# PMIC_Block.net
KiCad netlist of a schematic drawn in Altium Designer
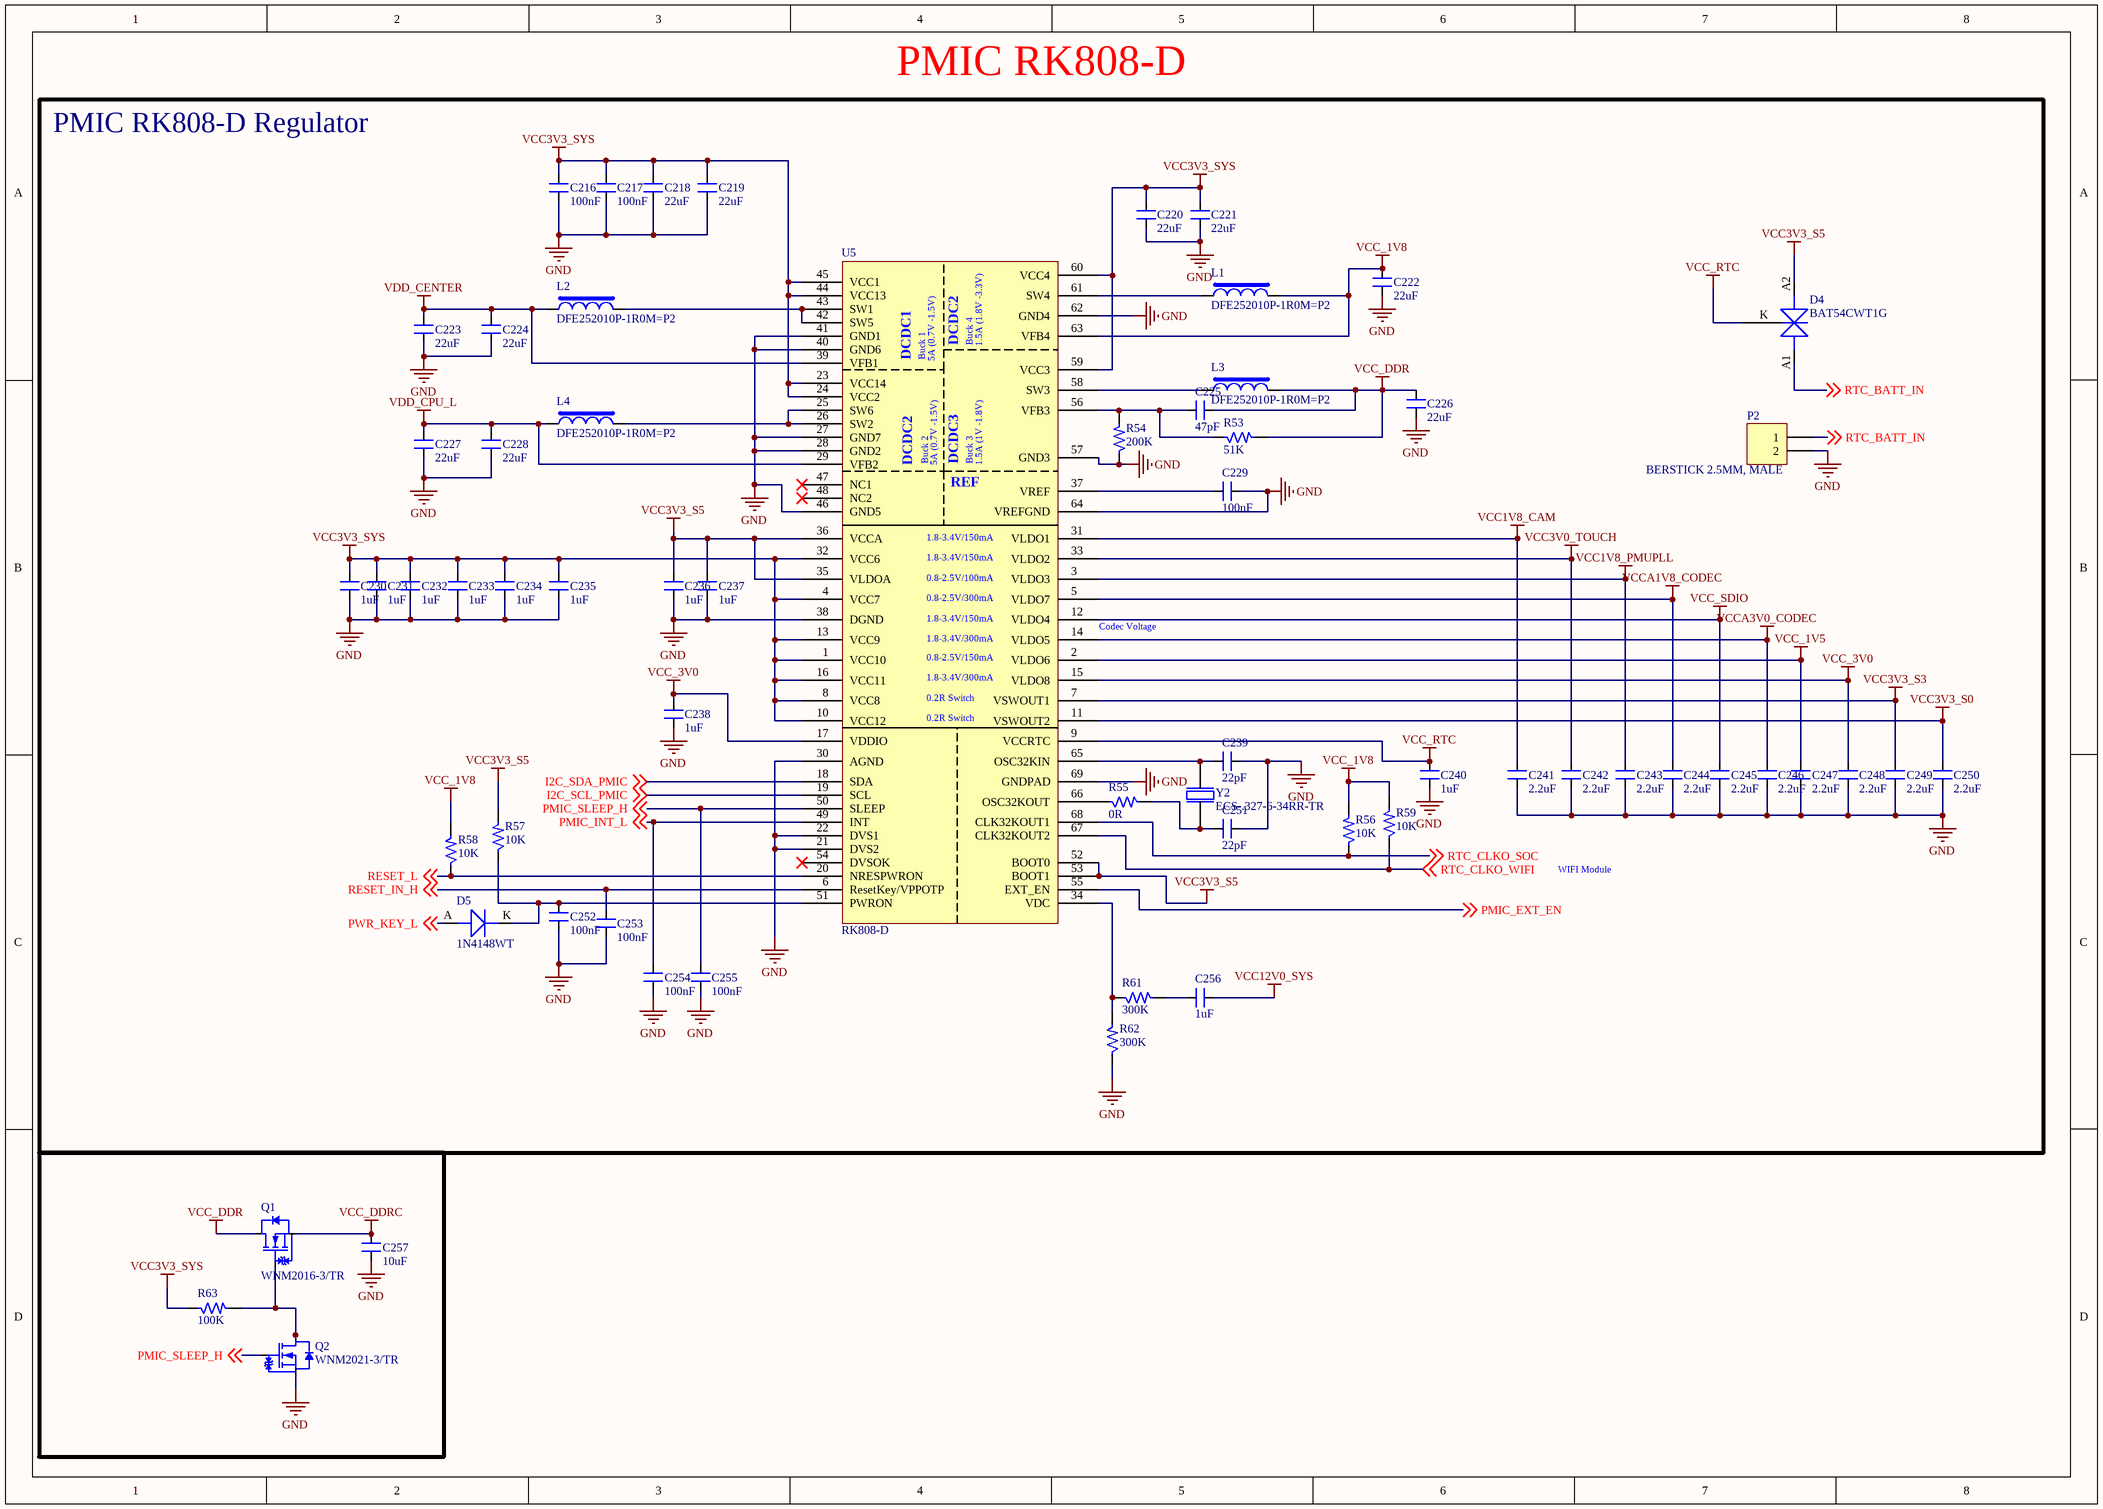
[diagram p0: PMIC_Block.SchDoc]

(export (version "E")
  (design (tool "Eeschema 10.0.6"))
  (components
    (comp (ref "C216")
      (value "100nF")
      (footprint "CAP_0402")
      (description "0.1µF ±10% 25V Ceramic Capacitor X7R 0402 (1005 Metric)")
      (fields
        (field (name "MANUFACTURER") "Walsin Technology Corporation")
        (field (name "MANUFACTURER PART NUMBER") "0402B104K250CT")
      )
      (libsource (lib "RK3399 _Module_Schlib") (part "CAP_100nF-25V-10%-0402"))
    )
    (comp (ref "C217")
      (value "100nF")
      (footprint "CAP_0402")
      (description "0.1µF ±10% 25V Ceramic Capacitor X7R 0402 (1005 Metric)")
      (fields
        (field (name "MANUFACTURER") "Walsin Technology Corporation")
        (field (name "MANUFACTURER PART NUMBER") "0402B104K250CT")
      )
      (libsource (lib "RK3399 _Module_Schlib") (part "CAP_100nF-25V-10%-0402"))
    )
    (comp (ref "C218")
      (value "22uF")
      (footprint "CAP_0603")
      (description "22µF ±20% 10V Ceramic Capacitor X5R 0603 (1608 Metric)")
      (fields
        (field (name "MANUFACTURER") "Murata Electronics")
        (field (name "MANUFACTURER PART NUMBER") "GRM188R61A226ME15D")
      )
      (libsource (lib "RK3399 _Module_Schlib") (part "CAP_22uF-10V-20%-0603"))
    )
    (comp (ref "C219")
      (value "22uF")
      (footprint "CAP_0603")
      (description "22µF ±20% 10V Ceramic Capacitor X5R 0603 (1608 Metric)")
      (fields
        (field (name "MANUFACTURER") "Murata Electronics")
        (field (name "MANUFACTURER PART NUMBER") "GRM188R61A226ME15D")
      )
      (libsource (lib "RK3399 _Module_Schlib") (part "CAP_22uF-10V-20%-0603"))
    )
    (comp (ref "C220")
      (value "22uF")
      (footprint "CAP_0603")
      (description "22µF ±20% 10V Ceramic Capacitor X5R 0603 (1608 Metric)")
      (fields
        (field (name "MANUFACTURER") "Murata Electronics")
        (field (name "MANUFACTURER PART NUMBER") "GRM188R61A226ME15D")
      )
      (libsource (lib "RK3399 _Module_Schlib") (part "CAP_22uF-10V-20%-0603"))
    )
    (comp (ref "C221")
      (value "22uF")
      (footprint "CAP_0603")
      (description "22µF ±20% 10V Ceramic Capacitor X5R 0603 (1608 Metric)")
      (fields
        (field (name "MANUFACTURER") "Murata Electronics")
        (field (name "MANUFACTURER PART NUMBER") "GRM188R61A226ME15D")
      )
      (libsource (lib "RK3399 _Module_Schlib") (part "CAP_22uF-10V-20%-0603"))
    )
    (comp (ref "C222")
      (value "22uF")
      (footprint "CAP_0603")
      (description "22µF ±20% 10V Ceramic Capacitor X5R 0603 (1608 Metric)")
      (fields
        (field (name "MANUFACTURER") "Murata Electronics")
        (field (name "MANUFACTURER PART NUMBER") "GRM188R61A226ME15D")
      )
      (libsource (lib "RK3399 _Module_Schlib") (part "CAP_22uF-10V-20%-0603"))
    )
    (comp (ref "C223")
      (value "22uF")
      (footprint "CAP_0603")
      (description "22µF ±20% 10V Ceramic Capacitor X5R 0603 (1608 Metric)")
      (fields
        (field (name "MANUFACTURER") "Murata Electronics")
        (field (name "MANUFACTURER PART NUMBER") "GRM188R61A226ME15D")
      )
      (libsource (lib "RK3399 _Module_Schlib") (part "CAP_22uF-10V-20%-0603"))
    )
    (comp (ref "C224")
      (value "22uF")
      (footprint "CAP_0603")
      (description "22µF ±20% 10V Ceramic Capacitor X5R 0603 (1608 Metric)")
      (fields
        (field (name "MANUFACTURER") "Murata Electronics")
        (field (name "MANUFACTURER PART NUMBER") "GRM188R61A226ME15D")
      )
      (libsource (lib "RK3399 _Module_Schlib") (part "CAP_22uF-10V-20%-0603"))
    )
    (comp (ref "C225")
      (value "47pF")
      (footprint "CAP_0402")
      (description "47pF ±10% 10V Ceramic Capacitor C0G, NP0 0402 (1005 Metric)")
      (fields
        (field (name "MANUFACTURER") "KEMET")
        (field (name "MANUFACTURER PART NUMBER") "C0402C470K8GAC7867")
      )
      (libsource (lib "RK3399 _Module_Schlib") (part "CAP_47pF-10V-10%-0402"))
    )
    (comp (ref "C226")
      (value "22uF")
      (footprint "CAP_0603")
      (description "22µF ±20% 10V Ceramic Capacitor X5R 0603 (1608 Metric)")
      (fields
        (field (name "MANUFACTURER") "Murata Electronics")
        (field (name "MANUFACTURER PART NUMBER") "GRM188R61A226ME15D")
      )
      (libsource (lib "RK3399 _Module_Schlib") (part "CAP_22uF-10V-20%-0603"))
    )
    (comp (ref "C227")
      (value "22uF")
      (footprint "CAP_0603")
      (description "22µF ±20% 10V Ceramic Capacitor X5R 0603 (1608 Metric)")
      (fields
        (field (name "MANUFACTURER") "Murata Electronics")
        (field (name "MANUFACTURER PART NUMBER") "GRM188R61A226ME15D")
      )
      (libsource (lib "RK3399 _Module_Schlib") (part "CAP_22uF-10V-20%-0603"))
    )
    (comp (ref "C228")
      (value "22uF")
      (footprint "CAP_0603")
      (description "22µF ±20% 10V Ceramic Capacitor X5R 0603 (1608 Metric)")
      (fields
        (field (name "MANUFACTURER") "Murata Electronics")
        (field (name "MANUFACTURER PART NUMBER") "GRM188R61A226ME15D")
      )
      (libsource (lib "RK3399 _Module_Schlib") (part "CAP_22uF-10V-20%-0603"))
    )
    (comp (ref "C229")
      (value "100nF")
      (footprint "CAP_0402")
      (description "0.1µF ±10% 25V Ceramic Capacitor X7R 0402 (1005 Metric)")
      (fields
        (field (name "MANUFACTURER") "Walsin Technology Corporation")
        (field (name "MANUFACTURER PART NUMBER") "0402B104K250CT")
      )
      (libsource (lib "RK3399 _Module_Schlib") (part "CAP_100nF-25V-10%-0402"))
    )
    (comp (ref "C230")
      (value "1uF")
      (footprint "CAP_0402")
      (description "1µF ±10% 16V Ceramic Capacitor X5R 0402 (1005 Metric)")
      (fields
        (field (name "MANUFACTURER") "Knowles Novacap")
        (field (name "MANUFACTURER PART NUMBER") "0402BW105K160YT")
      )
      (libsource (lib "RK3399 _Module_Schlib") (part "CAP_1uF-16V-10%-0402"))
    )
    (comp (ref "C231")
      (value "1uF")
      (footprint "CAP_0402")
      (description "1µF ±10% 16V Ceramic Capacitor X5R 0402 (1005 Metric)")
      (fields
        (field (name "MANUFACTURER") "Knowles Novacap")
        (field (name "MANUFACTURER PART NUMBER") "0402BW105K160YT")
      )
      (libsource (lib "RK3399 _Module_Schlib") (part "CAP_1uF-16V-10%-0402"))
    )
    (comp (ref "C232")
      (value "1uF")
      (footprint "CAP_0402")
      (description "1µF ±10% 16V Ceramic Capacitor X5R 0402 (1005 Metric)")
      (fields
        (field (name "MANUFACTURER") "Knowles Novacap")
        (field (name "MANUFACTURER PART NUMBER") "0402BW105K160YT")
      )
      (libsource (lib "RK3399 _Module_Schlib") (part "CAP_1uF-16V-10%-0402"))
    )
    (comp (ref "C233")
      (value "1uF")
      (footprint "CAP_0402")
      (description "1µF ±10% 16V Ceramic Capacitor X5R 0402 (1005 Metric)")
      (fields
        (field (name "MANUFACTURER") "Knowles Novacap")
        (field (name "MANUFACTURER PART NUMBER") "0402BW105K160YT")
      )
      (libsource (lib "RK3399 _Module_Schlib") (part "CAP_1uF-16V-10%-0402"))
    )
    (comp (ref "C234")
      (value "1uF")
      (footprint "CAP_0402")
      (description "1µF ±10% 16V Ceramic Capacitor X5R 0402 (1005 Metric)")
      (fields
        (field (name "MANUFACTURER") "Knowles Novacap")
        (field (name "MANUFACTURER PART NUMBER") "0402BW105K160YT")
      )
      (libsource (lib "RK3399 _Module_Schlib") (part "CAP_1uF-16V-10%-0402"))
    )
    (comp (ref "C235")
      (value "1uF")
      (footprint "CAP_0402")
      (description "1µF ±10% 16V Ceramic Capacitor X5R 0402 (1005 Metric)")
      (fields
        (field (name "MANUFACTURER") "Knowles Novacap")
        (field (name "MANUFACTURER PART NUMBER") "0402BW105K160YT")
      )
      (libsource (lib "RK3399 _Module_Schlib") (part "CAP_1uF-16V-10%-0402"))
    )
    (comp (ref "C236")
      (value "1uF")
      (footprint "CAP_0402")
      (description "1µF ±10% 16V Ceramic Capacitor X5R 0402 (1005 Metric)")
      (fields
        (field (name "MANUFACTURER") "Knowles Novacap")
        (field (name "MANUFACTURER PART NUMBER") "0402BW105K160YT")
      )
      (libsource (lib "RK3399 _Module_Schlib") (part "CAP_1uF-16V-10%-0402"))
    )
    (comp (ref "C237")
      (value "1uF")
      (footprint "CAP_0402")
      (description "1µF ±10% 16V Ceramic Capacitor X5R 0402 (1005 Metric)")
      (fields
        (field (name "MANUFACTURER") "Knowles Novacap")
        (field (name "MANUFACTURER PART NUMBER") "0402BW105K160YT")
      )
      (libsource (lib "RK3399 _Module_Schlib") (part "CAP_1uF-16V-10%-0402"))
    )
    (comp (ref "C238")
      (value "1uF")
      (footprint "CAP_0402")
      (description "1µF ±10% 16V Ceramic Capacitor X5R 0402 (1005 Metric)")
      (fields
        (field (name "MANUFACTURER") "Knowles Novacap")
        (field (name "MANUFACTURER PART NUMBER") "0402BW105K160YT")
      )
      (libsource (lib "RK3399 _Module_Schlib") (part "CAP_1uF-16V-10%-0402"))
    )
    (comp (ref "C239")
      (value "22pF")
      (footprint "CAP_0402")
      (description "22pF ±10% 10V Ceramic Capacitor C0G, NP0 0402 (1005 Metric)")
      (fields
        (field (name "MANUFACTURER") "KEMET")
        (field (name "MANUFACTURER PART NUMBER") "C0402C220K8GACTU")
      )
      (libsource (lib "RK3399 _Module_Schlib") (part "CAP_22pF-10V-10%-0402"))
    )
    (comp (ref "C240")
      (value "1uF")
      (footprint "CAP_0402")
      (description "1µF ±10% 16V Ceramic Capacitor X5R 0402 (1005 Metric)")
      (fields
        (field (name "MANUFACTURER") "Knowles Novacap")
        (field (name "MANUFACTURER PART NUMBER") "0402BW105K160YT")
      )
      (libsource (lib "RK3399 _Module_Schlib") (part "CAP_1uF-16V-10%-0402"))
    )
    (comp (ref "C241")
      (value "2.2uF")
      (footprint "CAP_0402")
      (description "2.2µF ±10% 10V Ceramic Capacitor X5R 0402 (1005 Metric)")
      (fields
        (field (name "MANUFACTURER") "Murata Electronics")
        (field (name "MANUFACTURER PART NUMBER") "GRM155R61A225KE95D")
      )
      (libsource (lib "RK3399 _Module_Schlib") (part "CAP_2.2uF-10V-10%-0402"))
    )
    (comp (ref "C242")
      (value "2.2uF")
      (footprint "CAP_0402")
      (description "2.2µF ±10% 10V Ceramic Capacitor X5R 0402 (1005 Metric)")
      (fields
        (field (name "MANUFACTURER") "Murata Electronics")
        (field (name "MANUFACTURER PART NUMBER") "GRM155R61A225KE95D")
      )
      (libsource (lib "RK3399 _Module_Schlib") (part "CAP_2.2uF-10V-10%-0402"))
    )
    (comp (ref "C243")
      (value "2.2uF")
      (footprint "CAP_0402")
      (description "2.2µF ±10% 10V Ceramic Capacitor X5R 0402 (1005 Metric)")
      (fields
        (field (name "MANUFACTURER") "Murata Electronics")
        (field (name "MANUFACTURER PART NUMBER") "GRM155R61A225KE95D")
      )
      (libsource (lib "RK3399 _Module_Schlib") (part "CAP_2.2uF-10V-10%-0402"))
    )
    (comp (ref "C244")
      (value "2.2uF")
      (footprint "CAP_0402")
      (description "2.2µF ±10% 10V Ceramic Capacitor X5R 0402 (1005 Metric)")
      (fields
        (field (name "MANUFACTURER") "Murata Electronics")
        (field (name "MANUFACTURER PART NUMBER") "GRM155R61A225KE95D")
      )
      (libsource (lib "RK3399 _Module_Schlib") (part "CAP_2.2uF-10V-10%-0402"))
    )
    (comp (ref "C245")
      (value "2.2uF")
      (footprint "CAP_0402")
      (description "2.2µF ±10% 10V Ceramic Capacitor X5R 0402 (1005 Metric)")
      (fields
        (field (name "MANUFACTURER") "Murata Electronics")
        (field (name "MANUFACTURER PART NUMBER") "GRM155R61A225KE95D")
      )
      (libsource (lib "RK3399 _Module_Schlib") (part "CAP_2.2uF-10V-10%-0402"))
    )
    (comp (ref "C246")
      (value "2.2uF")
      (footprint "CAP_0402")
      (description "2.2µF ±10% 10V Ceramic Capacitor X5R 0402 (1005 Metric)")
      (fields
        (field (name "MANUFACTURER") "Murata Electronics")
        (field (name "MANUFACTURER PART NUMBER") "GRM155R61A225KE95D")
      )
      (libsource (lib "RK3399 _Module_Schlib") (part "CAP_2.2uF-10V-10%-0402"))
    )
    (comp (ref "C247")
      (value "2.2uF")
      (footprint "CAP_0402")
      (description "2.2µF ±10% 10V Ceramic Capacitor X5R 0402 (1005 Metric)")
      (fields
        (field (name "MANUFACTURER") "Murata Electronics")
        (field (name "MANUFACTURER PART NUMBER") "GRM155R61A225KE95D")
      )
      (libsource (lib "RK3399 _Module_Schlib") (part "CAP_2.2uF-10V-10%-0402"))
    )
    (comp (ref "C248")
      (value "2.2uF")
      (footprint "CAP_0402")
      (description "2.2µF ±10% 10V Ceramic Capacitor X5R 0402 (1005 Metric)")
      (fields
        (field (name "MANUFACTURER") "Murata Electronics")
        (field (name "MANUFACTURER PART NUMBER") "GRM155R61A225KE95D")
      )
      (libsource (lib "RK3399 _Module_Schlib") (part "CAP_2.2uF-10V-10%-0402"))
    )
    (comp (ref "C249")
      (value "2.2uF")
      (footprint "CAP_0402")
      (description "2.2µF ±10% 10V Ceramic Capacitor X5R 0402 (1005 Metric)")
      (fields
        (field (name "MANUFACTURER") "Murata Electronics")
        (field (name "MANUFACTURER PART NUMBER") "GRM155R61A225KE95D")
      )
      (libsource (lib "RK3399 _Module_Schlib") (part "CAP_2.2uF-10V-10%-0402"))
    )
    (comp (ref "C250")
      (value "2.2uF")
      (footprint "CAP_0402")
      (description "2.2µF ±10% 10V Ceramic Capacitor X5R 0402 (1005 Metric)")
      (fields
        (field (name "MANUFACTURER") "Murata Electronics")
        (field (name "MANUFACTURER PART NUMBER") "GRM155R61A225KE95D")
      )
      (libsource (lib "RK3399 _Module_Schlib") (part "CAP_2.2uF-10V-10%-0402"))
    )
    (comp (ref "C251")
      (value "22pF")
      (footprint "CAP_0402")
      (description "22pF ±10% 10V Ceramic Capacitor C0G, NP0 0402 (1005 Metric)")
      (fields
        (field (name "MANUFACTURER") "KEMET")
        (field (name "MANUFACTURER PART NUMBER") "C0402C220K8GACTU")
      )
      (libsource (lib "RK3399 _Module_Schlib") (part "CAP_22pF-10V-10%-0402"))
    )
    (comp (ref "C252")
      (value "100nF")
      (footprint "CAP_0402")
      (description "0.1µF ±10% 25V Ceramic Capacitor X7R 0402 (1005 Metric)")
      (fields
        (field (name "MANUFACTURER") "Walsin Technology Corporation")
        (field (name "MANUFACTURER PART NUMBER") "0402B104K250CT")
      )
      (libsource (lib "RK3399 _Module_Schlib") (part "CAP_100nF-25V-10%-0402"))
    )
    (comp (ref "C253")
      (value "100nF")
      (footprint "CAP_0402")
      (description "0.1µF ±10% 25V Ceramic Capacitor X7R 0402 (1005 Metric)")
      (fields
        (field (name "MANUFACTURER") "Walsin Technology Corporation")
        (field (name "MANUFACTURER PART NUMBER") "0402B104K250CT")
      )
      (libsource (lib "RK3399 _Module_Schlib") (part "CAP_100nF-25V-10%-0402"))
    )
    (comp (ref "C254")
      (value "100nF")
      (footprint "CAP_0402")
      (description "0.1µF ±10% 25V Ceramic Capacitor X7R 0402 (1005 Metric)")
      (fields
        (field (name "MANUFACTURER") "Walsin Technology Corporation")
        (field (name "MANUFACTURER PART NUMBER") "0402B104K250CT")
      )
      (libsource (lib "RK3399 _Module_Schlib") (part "CAP_100nF-25V-10%-0402"))
    )
    (comp (ref "C255")
      (value "100nF")
      (footprint "CAP_0402")
      (description "0.1µF ±10% 25V Ceramic Capacitor X7R 0402 (1005 Metric)")
      (fields
        (field (name "MANUFACTURER") "Walsin Technology Corporation")
        (field (name "MANUFACTURER PART NUMBER") "0402B104K250CT")
      )
      (libsource (lib "RK3399 _Module_Schlib") (part "CAP_100nF-25V-10%-0402"))
    )
    (comp (ref "C256")
      (value "1uF")
      (footprint "CAP_0402")
      (description "1µF ±10% 16V Ceramic Capacitor X5R 0402 (1005 Metric)")
      (fields
        (field (name "MANUFACTURER") "Knowles Novacap")
        (field (name "MANUFACTURER PART NUMBER") "0402BW105K160YT")
      )
      (libsource (lib "RK3399 _Module_Schlib") (part "CAP_1uF-16V-10%-0402"))
    )
    (comp (ref "C257")
      (value "10uF")
      (footprint "CAP_0402")
      (description "10µF ±20% 10V Ceramic Capacitor X5R 0402 (1005 Metric)")
      (fields
        (field (name "MANUFACTURER PART NUMBER") "CL05A106MP5NUNC")
        (field (name "MANUFACTURER") "Samsung Electro-Mechanics")
      )
      (libsource (lib "RK3399 _Module_Schlib") (part "CAP_10uF-10V-20%-0402"))
    )
    (comp (ref "D4")
      (value "BAT54CWT1G")
      (footprint "DIO_SOT-323-3")
      (description "Diode Array 1 Pair Common Cathode Schottky 30V 200mA (DC) Surface Mount SC-70, SOT-323")
      (fields (field (name "MANUFACTURER") "ON Semiconductor"))
      (libsource (lib "RK3399 _Module_Schlib") (part "DIO-S-A_30V-200mA-SOT-323"))
    )
    (comp (ref "D5")
      (value "1N4148WT")
      (footprint "DIO_SOD523")
      (description "Diode Standard 100V 300mA (DC) Surface Mount SOD-123")
      (fields (field (name "MANUFACTURER") "FAIRCHILD"))
      (libsource (lib "RK3399 _Module_Schlib") (part "DIO_75V-200mA-SOD-523F"))
    )
    (comp (ref "L1")
      (value "DFE252010P-1R0M=P2")
      (footprint "IND_1008")
      (description "1µH Shielded Wirewound Inductor 3.8A 54mOhm Max 1008 (2520 Metric)")
      (fields (field (name "MANUFACTURER") "Murata Electronics"))
      (libsource (lib "RK3399 _Module_Schlib") (part "IND_1uH-3.8A-20%-1008"))
    )
    (comp (ref "L2")
      (value "DFE252010P-1R0M=P2")
      (footprint "IND_1008")
      (description "1µH Shielded Wirewound Inductor 3.8A 54mOhm Max 1008 (2520 Metric)")
      (fields (field (name "MANUFACTURER") "Murata Electronics"))
      (libsource (lib "RK3399 _Module_Schlib") (part "IND_1uH-3.8A-20%-1008"))
    )
    (comp (ref "L3")
      (value "DFE252010P-1R0M=P2")
      (footprint "IND_1008")
      (description "1µH Shielded Wirewound Inductor 3.8A 54mOhm Max 1008 (2520 Metric)")
      (fields (field (name "MANUFACTURER") "Murata Electronics"))
      (libsource (lib "RK3399 _Module_Schlib") (part "IND_1uH-3.8A-20%-1008"))
    )
    (comp (ref "L4")
      (value "DFE252010P-1R0M=P2")
      (footprint "IND_1008")
      (description "1µH Shielded Wirewound Inductor 3.8A 54mOhm Max 1008 (2520 Metric)")
      (fields (field (name "MANUFACTURER") "Murata Electronics"))
      (libsource (lib "RK3399 _Module_Schlib") (part "IND_1uH-3.8A-20%-1008"))
    )
    (comp (ref "P2")
      (value "BERSTICK 2.5MM, MALE")
      (footprint "CON2_100_43D62_TH_ST")
      (description "2 Pins, 1 Row 2.54mm Pitch, Straight bergstrip, Male")
      (fields (field (name "MANUFACTURER PART NUMBER") "NA") (field (name "MANUFACTURER") "Samtec"))
      (libsource (lib "EsteemPCB_COB_Course_intlib") (part "CON-BS-PLG_2X1-100-ST-TH"))
    )
    (comp (ref "Q1")
      (value "WNM2016-3/TR")
      (footprint "SOT 23-3")
      (description "N Channel 20V 2.9A 1V @ 250uA 47mΩ @ 3.6A,4.5V 700mW SOT-23(SOT-23-3) MOSFET RoHS")
      (fields (field (name "MANUFACTURER") "WILLSEMI(Will Semicon)"))
      (libsource (lib "RK3399 _Module_Schlib") (part "MOSFET-N_20V-2.9A-SOT-23"))
    )
    (comp (ref "Q2")
      (value "WNM2021-3/TR")
      (footprint "SOT-323-3")
      (description "N Channel 20V 820mA 850mV @ 250uA 310mΩ @ 550mA,4.5V 310mW SOT-323(SC-70) MOSFET RoHS")
      (fields (field (name "MANUFACTURER") "WILLSEMI(Will Semicon)"))
      (libsource (lib "RK3399 _Module_Schlib") (part "MOSFET-N_20V-820mA-SOT-323"))
    )
    (comp (ref "R53")
      (value "51K")
      (footprint "RES_0402")
      (description "51 kOhms ±1% 0.1W, 1/10W Chip Resistor 0402 (1005 Metric) Automotive AEC-Q200 Thick Film")
      (fields
        (field (name "MANUFACTURER") "Panasonic Electronic Components")
        (field (name "MANUFACTURER PART NUMBER") "ERJ-2RKF5102X")
      )
      (libsource (lib "RK3399 _Module_Schlib") (part "RES_51K-0.1W-1%-0402"))
    )
    (comp (ref "R54")
      (value "200K")
      (footprint "RES_0402")
      (description "200 kOhms ±1% 0.1W, 1/10W Chip Resistor 0402 (1005 Metric) Automotive AEC-Q200 Thick Film")
      (fields
        (field (name "MANUFACTURER") "Panasonic Electronic Components")
        (field (name "MANUFACTURER PART NUMBER") "ERJ-2RKF2003X")
      )
      (libsource (lib "RK3399 _Module_Schlib") (part "RES_200K-0.1W-1%-0402"))
    )
    (comp (ref "R55")
      (value "0R")
      (footprint "RES_0402")
      (description "0 Ohms Jumper 0.1W, 1/10W Chip Resistor 0402 (1005 Metric) Automotive AEC-Q200 Thick Film")
      (fields
        (field (name "MANUFACTURER") "Panasonic Electronic Components")
        (field (name "MANUFACTURER PART NUMBER") "ERJ-2GE0R00X")
      )
      (libsource (lib "RK3399 _Module_Schlib") (part "RES_0R-0.1W-1%-0402"))
    )
    (comp (ref "R56")
      (value "10K")
      (footprint "RES_0402")
      (description "10 kOhms ±1% 0.1W, 1/10W Chip Resistor 0402 (1005 Metric) Anti-Sulfur Thin Film")
      (fields
        (field (name "MANUFACTURER") "Vishay Beyschlag/Draloric/BC Components")
        (field (name "MANUFACTURER PART NUMBER") "MCS04020C1002FE000")
      )
      (libsource (lib "RK3399 _Module_Schlib") (part "RES_10K-0.1W-1%-0402"))
    )
    (comp (ref "R57")
      (value "10K")
      (footprint "RES_0402")
      (description "10 kOhms ±1% 0.1W, 1/10W Chip Resistor 0402 (1005 Metric) Anti-Sulfur Thin Film")
      (fields
        (field (name "MANUFACTURER") "Vishay Beyschlag/Draloric/BC Components")
        (field (name "MANUFACTURER PART NUMBER") "MCS04020C1002FE000")
      )
      (libsource (lib "RK3399 _Module_Schlib") (part "RES_10K-0.1W-1%-0402"))
    )
    (comp (ref "R58")
      (value "10K")
      (footprint "RES_0402")
      (description "10 kOhms ±1% 0.1W, 1/10W Chip Resistor 0402 (1005 Metric) Anti-Sulfur Thin Film")
      (fields
        (field (name "MANUFACTURER") "Vishay Beyschlag/Draloric/BC Components")
        (field (name "MANUFACTURER PART NUMBER") "MCS04020C1002FE000")
      )
      (libsource (lib "RK3399 _Module_Schlib") (part "RES_10K-0.1W-1%-0402"))
    )
    (comp (ref "R59")
      (value "10K")
      (footprint "RES_0402")
      (description "10 kOhms ±1% 0.1W, 1/10W Chip Resistor 0402 (1005 Metric) Anti-Sulfur Thin Film")
      (fields
        (field (name "MANUFACTURER") "Vishay Beyschlag/Draloric/BC Components")
        (field (name "MANUFACTURER PART NUMBER") "MCS04020C1002FE000")
      )
      (libsource (lib "RK3399 _Module_Schlib") (part "RES_10K-0.1W-1%-0402"))
    )
    (comp (ref "R61")
      (value "300K")
      (footprint "RES_0402")
      (description "300 kOhms ±1% 0.1W, 1/10W Chip Resistor 0402 (1005 Metric) Automotive AEC-Q200 Thick Film")
      (fields
        (field (name "MANUFACTURER") "Panasonic Electronic Components")
        (field (name "MANUFACTURER PART NUMBER") "ERJ-2RKF3003X")
      )
      (libsource (lib "RK3399 _Module_Schlib") (part "RES_300K-0.1W-1%-0402"))
    )
    (comp (ref "R62")
      (value "300K")
      (footprint "RES_0402")
      (description "300 kOhms ±1% 0.1W, 1/10W Chip Resistor 0402 (1005 Metric) Automotive AEC-Q200 Thick Film")
      (fields
        (field (name "MANUFACTURER") "Panasonic Electronic Components")
        (field (name "MANUFACTURER PART NUMBER") "ERJ-2RKF3003X")
      )
      (libsource (lib "RK3399 _Module_Schlib") (part "RES_300K-0.1W-1%-0402"))
    )
    (comp (ref "R63")
      (value "100K")
      (footprint "RES_0402")
      (description "100 kOhms ±1% 0.1W, 1/10W Chip Resistor 0402 (1005 Metric) Anti-Sulfur Thin Film")
      (fields
        (field (name "MANUFACTURER") "Vishay Beyschlag/Draloric/BC Components")
        (field (name "MANUFACTURER PART NUMBER") "MCS04020C1003FE000")
      )
      (libsource (lib "RK3399 _Module_Schlib") (part "RES_100K-0.1W-1%-0402"))
    )
    (comp (ref "U5")
      (value "RK808-D")
      (footprint "QFN68_13.7_220.4X220.4_SMD")
      (description "The RK808 is a complete power supply solution for Portable systems.")
      (fields (field (name "MANUFACTURER") "Rockchip"))
      (libsource (lib "RK3399 _Module_Schlib") (part "IC_RK808-D-QFN68"))
    )
    (comp (ref "Y2")
      (value "ECS-.327-6-34RR-TR")
      (footprint "XTAL_ECS-.327-6-34RR-TR")
      (description "32.768kHz ±20ppm Crystal 12pF 80 kOhms 2-SMD, No Lead")
      (fields (field (name "MANUFACTURER") "Ecliptek"))
      (libsource (lib "RK3399 _Module_Schlib") (part "XTAL_32.768Khz-22pF-SMD"))
    )
  )
  (nets
    (net (code "1") (name "GND") (class "Default")
      (node (ref "C216") (pin "1") (pinfunction "1_1") (pintype "passive"))
      (node (ref "C217") (pin "1") (pinfunction "1_1") (pintype "passive"))
      (node (ref "C218") (pin "1") (pinfunction "1_1") (pintype "passive"))
      (node (ref "C219") (pin "1") (pinfunction "1_1") (pintype "passive"))
      (node (ref "C220") (pin "1") (pinfunction "1_1") (pintype "passive"))
      (node (ref "C221") (pin "1") (pinfunction "1_1") (pintype "passive"))
      (node (ref "C222") (pin "1") (pinfunction "1_1") (pintype "passive"))
      (node (ref "C223") (pin "1") (pinfunction "1_1") (pintype "passive"))
      (node (ref "C224") (pin "1") (pinfunction "1_1") (pintype "passive"))
      (node (ref "C226") (pin "1") (pinfunction "1_1") (pintype "passive"))
      (node (ref "C227") (pin "1") (pinfunction "1_1") (pintype "passive"))
      (node (ref "C228") (pin "1") (pinfunction "1_1") (pintype "passive"))
      (node (ref "C229") (pin "1") (pinfunction "1_1") (pintype "passive"))
      (node (ref "C230") (pin "2") (pinfunction "2_2") (pintype "passive"))
      (node (ref "C231") (pin "1") (pinfunction "1_1") (pintype "passive"))
      (node (ref "C232") (pin "1") (pinfunction "1_1") (pintype "passive"))
      (node (ref "C233") (pin "1") (pinfunction "1_1") (pintype "passive"))
      (node (ref "C234") (pin "1") (pinfunction "1_1") (pintype "passive"))
      (node (ref "C235") (pin "1") (pinfunction "1_1") (pintype "passive"))
      (node (ref "C236") (pin "1") (pinfunction "1_1") (pintype "passive"))
      (node (ref "C237") (pin "1") (pinfunction "1_1") (pintype "passive"))
      (node (ref "C238") (pin "1") (pinfunction "1_1") (pintype "passive"))
      (node (ref "C239") (pin "2") (pinfunction "2_2") (pintype "passive"))
      (node (ref "C240") (pin "1") (pinfunction "1_1") (pintype "passive"))
      (node (ref "C241") (pin "1") (pinfunction "1_1") (pintype "passive"))
      (node (ref "C242") (pin "1") (pinfunction "1_1") (pintype "passive"))
      (node (ref "C243") (pin "1") (pinfunction "1_1") (pintype "passive"))
      (node (ref "C244") (pin "1") (pinfunction "1_1") (pintype "passive"))
      (node (ref "C245") (pin "1") (pinfunction "1_1") (pintype "passive"))
      (node (ref "C246") (pin "1") (pinfunction "1_1") (pintype "passive"))
      (node (ref "C247") (pin "1") (pinfunction "1_1") (pintype "passive"))
      (node (ref "C248") (pin "1") (pinfunction "1_1") (pintype "passive"))
      (node (ref "C249") (pin "1") (pinfunction "1_1") (pintype "passive"))
      (node (ref "C250") (pin "1") (pinfunction "1_1") (pintype "passive"))
      (node (ref "C251") (pin "2") (pinfunction "2_2") (pintype "passive"))
      (node (ref "C252") (pin "1") (pinfunction "1_1") (pintype "passive"))
      (node (ref "C253") (pin "1") (pinfunction "1_1") (pintype "passive"))
      (node (ref "C254") (pin "1") (pinfunction "1_1") (pintype "passive"))
      (node (ref "C255") (pin "1") (pinfunction "1_1") (pintype "passive"))
      (node (ref "C257") (pin "1") (pinfunction "1_1") (pintype "passive"))
      (node (ref "P2") (pin "2") (pinfunction "2_2") (pintype "passive"))
      (node (ref "Q2") (pin "2") (pinfunction "S_2") (pintype "passive"))
      (node (ref "R54") (pin "1") (pinfunction "1_1") (pintype "passive"))
      (node (ref "R62") (pin "1") (pinfunction "1_1") (pintype "passive"))
      (node (ref "U5") (pin "21") (pinfunction "DVS2_21") (pintype "passive"))
      (node (ref "U5") (pin "22") (pinfunction "DVS1_22") (pintype "passive"))
      (node (ref "U5") (pin "27") (pinfunction "GND7_27") (pintype "passive"))
      (node (ref "U5") (pin "28") (pinfunction "GND2_28") (pintype "passive"))
      (node (ref "U5") (pin "30") (pinfunction "AGND_30") (pintype "passive"))
      (node (ref "U5") (pin "38") (pinfunction "DGND_38") (pintype "passive"))
      (node (ref "U5") (pin "40") (pinfunction "GND6_40") (pintype "passive"))
      (node (ref "U5") (pin "41") (pinfunction "GND1_41") (pintype "passive"))
      (node (ref "U5") (pin "46") (pinfunction "GND5_46") (pintype "passive"))
      (node (ref "U5") (pin "57") (pinfunction "GND3_57") (pintype "passive"))
      (node (ref "U5") (pin "62") (pinfunction "GND4_62") (pintype "passive"))
      (node (ref "U5") (pin "64") (pinfunction "VREFGND_64") (pintype "passive"))
      (node (ref "U5") (pin "69") (pinfunction "GNDPAD_69") (pintype "passive"))
    )
    (net (code "2") (name "I2C_SCL_PMIC") (class "Default")
      (node (ref "U5") (pin "19") (pinfunction "SCL_19") (pintype "passive"))
    )
    (net (code "3") (name "I2C_SDA_PMIC") (class "Default")
      (node (ref "U5") (pin "18") (pinfunction "SDA_18") (pintype "passive"))
    )
    (net (code "4") (name "Net-(C251-Pad1)") (class "Default")
      (node (ref "C251") (pin "1") (pinfunction "1_1") (pintype "passive"))
      (node (ref "R55") (pin "2") (pinfunction "2_2") (pintype "passive"))
      (node (ref "Y2") (pin "1") (pinfunction "1_1") (pintype "passive"))
    )
    (net (code "5") (name "Net-(C256-Pad2)") (class "Default")
      (node (ref "C256") (pin "2") (pinfunction "2_2") (pintype "passive"))
      (node (ref "R61") (pin "2") (pinfunction "2_2") (pintype "passive"))
    )
    (net (code "6") (name "Net-(D5-CATHODE)") (class "Default")
      (node (ref "C252") (pin "2") (pinfunction "2_2") (pintype "passive"))
      (node (ref "D5") (pin "K") (pinfunction "CATHODE_K") (pintype "passive"))
      (node (ref "R57") (pin "1") (pinfunction "1_1") (pintype "passive"))
      (node (ref "U5") (pin "51") (pinfunction "PWRON_51") (pintype "passive"))
    )
    (net (code "7") (name "Net-(Q1-G)") (class "Default")
      (node (ref "Q1") (pin "1") (pinfunction "G_1") (pintype "passive"))
      (node (ref "Q2") (pin "3") (pinfunction "D_3") (pintype "passive"))
      (node (ref "R63") (pin "2") (pinfunction "2_2") (pintype "passive"))
    )
    (net (code "8") (name "Net-(U5-OSC32KIN)") (class "Default")
      (node (ref "C239") (pin "1") (pinfunction "1_1") (pintype "passive"))
      (node (ref "U5") (pin "65") (pinfunction "OSC32KIN_65") (pintype "passive"))
      (node (ref "Y2") (pin "2") (pinfunction "2_2") (pintype "passive"))
    )
    (net (code "9") (name "Net-(U5-OSC32KOUT)") (class "Default")
      (node (ref "R55") (pin "1") (pinfunction "1_1") (pintype "passive"))
      (node (ref "U5") (pin "66") (pinfunction "OSC32KOUT_66") (pintype "passive"))
    )
    (net (code "10") (name "Net-(U5-SW1)") (class "Default")
      (node (ref "L2") (pin "2") (pinfunction "2_2") (pintype "passive"))
      (node (ref "U5") (pin "42") (pinfunction "SW5_42") (pintype "passive"))
      (node (ref "U5") (pin "43") (pinfunction "SW1_43") (pintype "passive"))
    )
    (net (code "11") (name "Net-(U5-SW2)") (class "Default")
      (node (ref "L4") (pin "2") (pinfunction "2_2") (pintype "passive"))
      (node (ref "U5") (pin "25") (pinfunction "SW6_25") (pintype "passive"))
      (node (ref "U5") (pin "26") (pinfunction "SW2_26") (pintype "passive"))
    )
    (net (code "12") (name "Net-(U5-SW3)") (class "Default")
      (node (ref "L3") (pin "1") (pinfunction "1_1") (pintype "passive"))
      (node (ref "U5") (pin "58") (pinfunction "SW3_58") (pintype "passive"))
    )
    (net (code "13") (name "Net-(U5-SW4)") (class "Default")
      (node (ref "L1") (pin "1") (pinfunction "1_1") (pintype "passive"))
      (node (ref "U5") (pin "61") (pinfunction "SW4_61") (pintype "passive"))
    )
    (net (code "14") (name "Net-(U5-VDC)") (class "Default")
      (node (ref "R61") (pin "1") (pinfunction "1_1") (pintype "passive"))
      (node (ref "R62") (pin "2") (pinfunction "2_2") (pintype "passive"))
      (node (ref "U5") (pin "34") (pinfunction "VDC_34") (pintype "passive"))
    )
    (net (code "15") (name "Net-(U5-VFB3)") (class "Default")
      (node (ref "C225") (pin "1") (pinfunction "1_1") (pintype "passive"))
      (node (ref "R53") (pin "1") (pinfunction "1_1") (pintype "passive"))
      (node (ref "R54") (pin "2") (pinfunction "2_2") (pintype "passive"))
      (node (ref "U5") (pin "56") (pinfunction "VFB3_56") (pintype "passive"))
    )
    (net (code "16") (name "Net-(U5-VREF)") (class "Default")
      (node (ref "C229") (pin "2") (pinfunction "2_2") (pintype "passive"))
      (node (ref "U5") (pin "37") (pinfunction "VREF_37") (pintype "passive"))
    )
    (net (code "17") (name "PMIC_EXT_EN") (class "Default")
      (node (ref "U5") (pin "55") (pinfunction "EXT_EN_55") (pintype "passive"))
    )
    (net (code "18") (name "PMIC_INT_L") (class "Default")
      (node (ref "C254") (pin "2") (pinfunction "2_2") (pintype "passive"))
      (node (ref "U5") (pin "49") (pinfunction "INT_49") (pintype "passive"))
    )
    (net (code "19") (name "PMIC_SLEEP_H") (class "Default")
      (node (ref "C255") (pin "2") (pinfunction "2_2") (pintype "passive"))
      (node (ref "Q2") (pin "1") (pinfunction "G_1") (pintype "passive"))
      (node (ref "U5") (pin "50") (pinfunction "SLEEP_50") (pintype "passive"))
    )
    (net (code "20") (name "PWR_KEY_L") (class "Default")
      (node (ref "D5") (pin "A") (pinfunction "ANODE_A") (pintype "passive"))
    )
    (net (code "21") (name "RESET_IN_H") (class "Default")
      (node (ref "C253") (pin "2") (pinfunction "2_2") (pintype "passive"))
      (node (ref "U5") (pin "6") (pinfunction "ResetKey/VPPOTP_6") (pintype "passive"))
    )
    (net (code "22") (name "RESET_L") (class "Default")
      (node (ref "R58") (pin "1") (pinfunction "1_1") (pintype "passive"))
      (node (ref "U5") (pin "20") (pinfunction "NRESPWRON_20") (pintype "passive"))
    )
    (net (code "23") (name "RTC_BATT_IN") (class "Default")
      (node (ref "D4") (pin "A1") (pinfunction "A1_A1") (pintype "passive"))
      (node (ref "P2") (pin "1") (pinfunction "1_1") (pintype "passive"))
    )
    (net (code "24") (name "RTC_CLKO_SOC") (class "Default")
      (node (ref "R56") (pin "1") (pinfunction "1_1") (pintype "passive"))
      (node (ref "U5") (pin "68") (pinfunction "CLK32KOUT1_68") (pintype "passive"))
    )
    (net (code "25") (name "RTC_CLKO_WIFI") (class "Default")
      (node (ref "R59") (pin "1") (pinfunction "1_1") (pintype "passive"))
      (node (ref "U5") (pin "67") (pinfunction "CLK32KOUT2_67") (pintype "passive"))
    )
    (net (code "26") (name "VCC1V8_CAM") (class "Default")
      (node (ref "C241") (pin "2") (pinfunction "2_2") (pintype "passive"))
      (node (ref "U5") (pin "31") (pinfunction "VLDO1_31") (pintype "passive"))
    )
    (net (code "27") (name "VCC1V8_PMUPLL") (class "Default")
      (node (ref "C243") (pin "2") (pinfunction "2_2") (pintype "passive"))
      (node (ref "U5") (pin "3") (pinfunction "VLDO3_3") (pintype "passive"))
    )
    (net (code "28") (name "VCC3V0_TOUCH") (class "Default")
      (node (ref "C242") (pin "2") (pinfunction "2_2") (pintype "passive"))
      (node (ref "U5") (pin "33") (pinfunction "VLDO2_33") (pintype "passive"))
    )
    (net (code "29") (name "VCC3V3_S0") (class "Default")
      (node (ref "C250") (pin "2") (pinfunction "2_2") (pintype "passive"))
      (node (ref "U5") (pin "11") (pinfunction "VSWOUT2_11") (pintype "passive"))
    )
    (net (code "30") (name "VCC3V3_S3") (class "Default")
      (node (ref "C249") (pin "2") (pinfunction "2_2") (pintype "passive"))
      (node (ref "U5") (pin "7") (pinfunction "VSWOUT1_7") (pintype "passive"))
    )
    (net (code "31") (name "VCC3V3_S5") (class "Default")
      (node (ref "C236") (pin "2") (pinfunction "2_2") (pintype "passive"))
      (node (ref "C237") (pin "2") (pinfunction "2_2") (pintype "passive"))
      (node (ref "D4") (pin "A2") (pinfunction "A2_A2") (pintype "passive"))
      (node (ref "R57") (pin "2") (pinfunction "2_2") (pintype "passive"))
      (node (ref "U5") (pin "35") (pinfunction "VLDOA_35") (pintype "passive"))
      (node (ref "U5") (pin "36") (pinfunction "VCCA_36") (pintype "passive"))
      (node (ref "U5") (pin "52") (pinfunction "BOOT0_52") (pintype "passive"))
      (node (ref "U5") (pin "53") (pinfunction "BOOT1_53") (pintype "passive"))
    )
    (net (code "32") (name "VCC3V3_SYS") (class "Default")
      (node (ref "C216") (pin "2") (pinfunction "2_2") (pintype "passive"))
      (node (ref "C217") (pin "2") (pinfunction "2_2") (pintype "passive"))
      (node (ref "C218") (pin "2") (pinfunction "2_2") (pintype "passive"))
      (node (ref "C219") (pin "2") (pinfunction "2_2") (pintype "passive"))
      (node (ref "C220") (pin "2") (pinfunction "2_2") (pintype "passive"))
      (node (ref "C221") (pin "2") (pinfunction "2_2") (pintype "passive"))
      (node (ref "C230") (pin "1") (pinfunction "1_1") (pintype "passive"))
      (node (ref "C231") (pin "2") (pinfunction "2_2") (pintype "passive"))
      (node (ref "C232") (pin "2") (pinfunction "2_2") (pintype "passive"))
      (node (ref "C233") (pin "2") (pinfunction "2_2") (pintype "passive"))
      (node (ref "C234") (pin "2") (pinfunction "2_2") (pintype "passive"))
      (node (ref "C235") (pin "2") (pinfunction "2_2") (pintype "passive"))
      (node (ref "R63") (pin "1") (pinfunction "1_1") (pintype "passive"))
      (node (ref "U5") (pin "1") (pinfunction "VCC10_1") (pintype "passive"))
      (node (ref "U5") (pin "10") (pinfunction "VCC12_10") (pintype "passive"))
      (node (ref "U5") (pin "13") (pinfunction "VCC9_13") (pintype "passive"))
      (node (ref "U5") (pin "16") (pinfunction "VCC11_16") (pintype "passive"))
      (node (ref "U5") (pin "23") (pinfunction "VCC14_23") (pintype "passive"))
      (node (ref "U5") (pin "24") (pinfunction "VCC2_24") (pintype "passive"))
      (node (ref "U5") (pin "32") (pinfunction "VCC6_32") (pintype "passive"))
      (node (ref "U5") (pin "4") (pinfunction "VCC7_4") (pintype "passive"))
      (node (ref "U5") (pin "44") (pinfunction "VCC13_44") (pintype "passive"))
      (node (ref "U5") (pin "45") (pinfunction "VCC1_45") (pintype "passive"))
      (node (ref "U5") (pin "59") (pinfunction "VCC3_59") (pintype "passive"))
      (node (ref "U5") (pin "60") (pinfunction "VCC4_60") (pintype "passive"))
      (node (ref "U5") (pin "8") (pinfunction "VCC8_8") (pintype "passive"))
    )
    (net (code "33") (name "VCC12V0_SYS") (class "Default")
      (node (ref "C256") (pin "1") (pinfunction "1_1") (pintype "passive"))
    )
    (net (code "34") (name "VCCA1V8_CODEC") (class "Default")
      (node (ref "C244") (pin "2") (pinfunction "2_2") (pintype "passive"))
      (node (ref "U5") (pin "5") (pinfunction "VLDO7_5") (pintype "passive"))
    )
    (net (code "35") (name "VCCA3V0_CODEC") (class "Default")
      (node (ref "C246") (pin "2") (pinfunction "2_2") (pintype "passive"))
      (node (ref "U5") (pin "14") (pinfunction "VLDO5_14") (pintype "passive"))
    )
    (net (code "36") (name "VCC_1V5") (class "Default")
      (node (ref "C247") (pin "2") (pinfunction "2_2") (pintype "passive"))
      (node (ref "U5") (pin "2") (pinfunction "VLDO6_2") (pintype "passive"))
    )
    (net (code "37") (name "VCC_1V8") (class "Default")
      (node (ref "C222") (pin "2") (pinfunction "2_2") (pintype "passive"))
      (node (ref "L1") (pin "2") (pinfunction "2_2") (pintype "passive"))
      (node (ref "R56") (pin "2") (pinfunction "2_2") (pintype "passive"))
      (node (ref "R58") (pin "2") (pinfunction "2_2") (pintype "passive"))
      (node (ref "R59") (pin "2") (pinfunction "2_2") (pintype "passive"))
      (node (ref "U5") (pin "63") (pinfunction "VFB4_63") (pintype "passive"))
    )
    (net (code "38") (name "VCC_3V0") (class "Default")
      (node (ref "C238") (pin "2") (pinfunction "2_2") (pintype "passive"))
      (node (ref "C248") (pin "2") (pinfunction "2_2") (pintype "passive"))
      (node (ref "U5") (pin "15") (pinfunction "VLDO8_15") (pintype "passive"))
      (node (ref "U5") (pin "17") (pinfunction "VDDIO_17") (pintype "passive"))
    )
    (net (code "39") (name "VCC_DDR") (class "Default")
      (node (ref "C225") (pin "2") (pinfunction "2_2") (pintype "passive"))
      (node (ref "C226") (pin "2") (pinfunction "2_2") (pintype "passive"))
      (node (ref "L3") (pin "2") (pinfunction "2_2") (pintype "passive"))
      (node (ref "Q1") (pin "3") (pinfunction "D_3") (pintype "passive"))
      (node (ref "R53") (pin "2") (pinfunction "2_2") (pintype "passive"))
    )
    (net (code "40") (name "VCC_DDRC") (class "Default")
      (node (ref "C257") (pin "2") (pinfunction "2_2") (pintype "passive"))
      (node (ref "Q1") (pin "2") (pinfunction "S_2") (pintype "passive"))
    )
    (net (code "41") (name "VCC_RTC") (class "Default")
      (node (ref "C240") (pin "2") (pinfunction "2_2") (pintype "passive"))
      (node (ref "D4") (pin "K") (pinfunction "K_K") (pintype "passive"))
      (node (ref "U5") (pin "9") (pinfunction "VCCRTC_9") (pintype "passive"))
    )
    (net (code "42") (name "VCC_SDIO") (class "Default")
      (node (ref "C245") (pin "2") (pinfunction "2_2") (pintype "passive"))
      (node (ref "U5") (pin "12") (pinfunction "VLDO4_12") (pintype "passive"))
    )
    (net (code "43") (name "VDD_CENTER") (class "Default")
      (node (ref "C223") (pin "2") (pinfunction "2_2") (pintype "passive"))
      (node (ref "C224") (pin "2") (pinfunction "2_2") (pintype "passive"))
      (node (ref "L2") (pin "1") (pinfunction "1_1") (pintype "passive"))
      (node (ref "U5") (pin "39") (pinfunction "VFB1_39") (pintype "passive"))
    )
    (net (code "44") (name "VDD_CPU_L") (class "Default")
      (node (ref "C227") (pin "2") (pinfunction "2_2") (pintype "passive"))
      (node (ref "C228") (pin "2") (pinfunction "2_2") (pintype "passive"))
      (node (ref "L4") (pin "1") (pinfunction "1_1") (pintype "passive"))
      (node (ref "U5") (pin "29") (pinfunction "VFB2_29") (pintype "passive"))
    )
    (net (code "45") (name "unconnected-(U5-DVSOK-Pad54)") (class "Default")
      (node (ref "U5") (pin "54") (pinfunction "DVSOK_54") (pintype "passive+no_connect"))
    )
    (net (code "46") (name "unconnected-(U5-NC1-Pad47)") (class "Default")
      (node (ref "U5") (pin "47") (pinfunction "NC1_47") (pintype "passive+no_connect"))
    )
    (net (code "47") (name "unconnected-(U5-NC2-Pad48)") (class "Default")
      (node (ref "U5") (pin "48") (pinfunction "NC2_48") (pintype "passive+no_connect"))
    )
  )
)
